# Support_NODE.net
KiCad netlist of a schematic drawn in Altium Designer
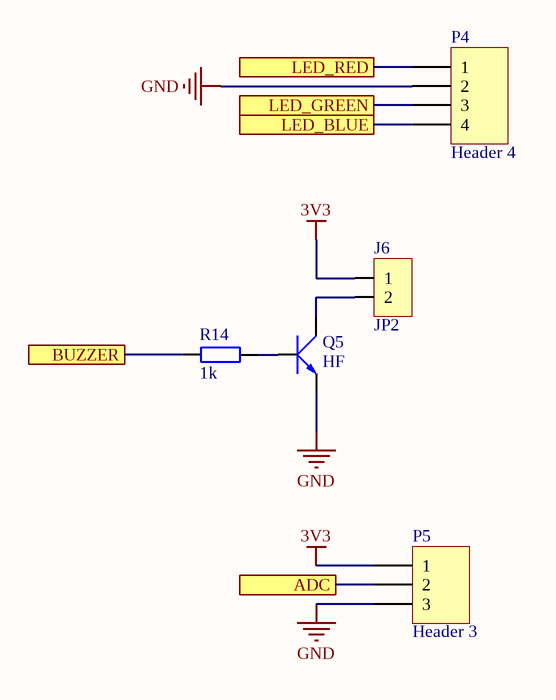
[diagram p0: Support_NODE.SchDoc]

(export (version "E")
  (design (tool "Eeschema 10.0.6"))
  (components
    (comp (ref "J6")
      (value "JP2")
      (footprint "JP2-D1T")
      (description "WR-PHD 2.54 mm Angled Socket Header")
      (fields
        (field (name "MANUFACTURER") "Würth Elektronik eiSos GmbH")
        (field (name "PARTNO") "613002143121")
        (field (name "CREATED BY") "Karrer Zheng")
      )
      (libsource (lib "My Library") (part "JP2"))
    )
    (comp (ref "P4")
      (value "Header 4")
      (footprint "Header 4")
      (description "Header, 4-Pin")
      (fields (field (name "PUBLISHER") "Altium Limited"))
      (libsource (lib "hphonglib") (part "Header 4"))
    )
    (comp (ref "P5")
      (value "Header 3")
      (footprint "Header 3")
      (description "Header, 3-Pin")
      (fields (field (name "PUBLISHER") "Altium Limited"))
      (libsource (lib "hphonglib") (part "Header 3"))
    )
    (comp (ref "Q5")
      (value "HF")
      (footprint "SOT23")
      (description "NPN transistor")
      (libsource (lib "TranFet") (part "C1815 HF SMD"))
    )
    (comp (ref "R14")
      (value "1k")
      (footprint "RES-SMD-0603")
      (description "Resistor SMD")
      (fields
        (field (name "MANUFACTURER") "Generic Components")
        (field (name "PUBLISHER") "Altium Hobart Technology Centre")
      )
      (libsource (lib "My Library") (part "Resistor - SMD"))
    )
  )
  (nets
    (net (code "1") (name "/ADC") (class "Default")
      (node (ref "P5") (pin "2") (pinfunction "2_2") (pintype "passive"))
    )
    (net (code "2") (name "/BUZZER") (class "Default")
      (node (ref "R14") (pin "2") (pinfunction "2_2") (pintype "passive"))
    )
    (net (code "3") (name "/LED_BLUE") (class "Default")
      (node (ref "P4") (pin "4") (pinfunction "4_4") (pintype "passive"))
    )
    (net (code "4") (name "/LED_GREEN") (class "Default")
      (node (ref "P4") (pin "3") (pinfunction "3_3") (pintype "passive"))
    )
    (net (code "5") (name "/LED_RED") (class "Default")
      (node (ref "P4") (pin "1") (pinfunction "1_1") (pintype "passive"))
    )
    (net (code "6") (name "3V3") (class "Default")
      (node (ref "J6") (pin "1") (pinfunction "1_1") (pintype "passive"))
      (node (ref "P5") (pin "1") (pinfunction "1_1") (pintype "passive"))
    )
    (net (code "7") (name "GND") (class "Default")
      (node (ref "P4") (pin "2") (pinfunction "2_2") (pintype "passive"))
      (node (ref "P5") (pin "3") (pinfunction "3_3") (pintype "passive"))
      (node (ref "Q5") (pin "2") (pinfunction "E_2") (pintype "passive"))
    )
    (net (code "8") (name "Net-(Q5-B)") (class "Default")
      (node (ref "Q5") (pin "1") (pinfunction "B_1") (pintype "passive"))
      (node (ref "R14") (pin "1") (pinfunction "1_1") (pintype "passive"))
    )
    (net (code "9") (name "Net-(Q5-C)") (class "Default")
      (node (ref "J6") (pin "2") (pinfunction "2_2") (pintype "passive"))
      (node (ref "Q5") (pin "3") (pinfunction "C_3") (pintype "passive"))
    )
  )
)
